# IGauge_V_2_0.net
KiCad netlist of a schematic drawn in EAGLE
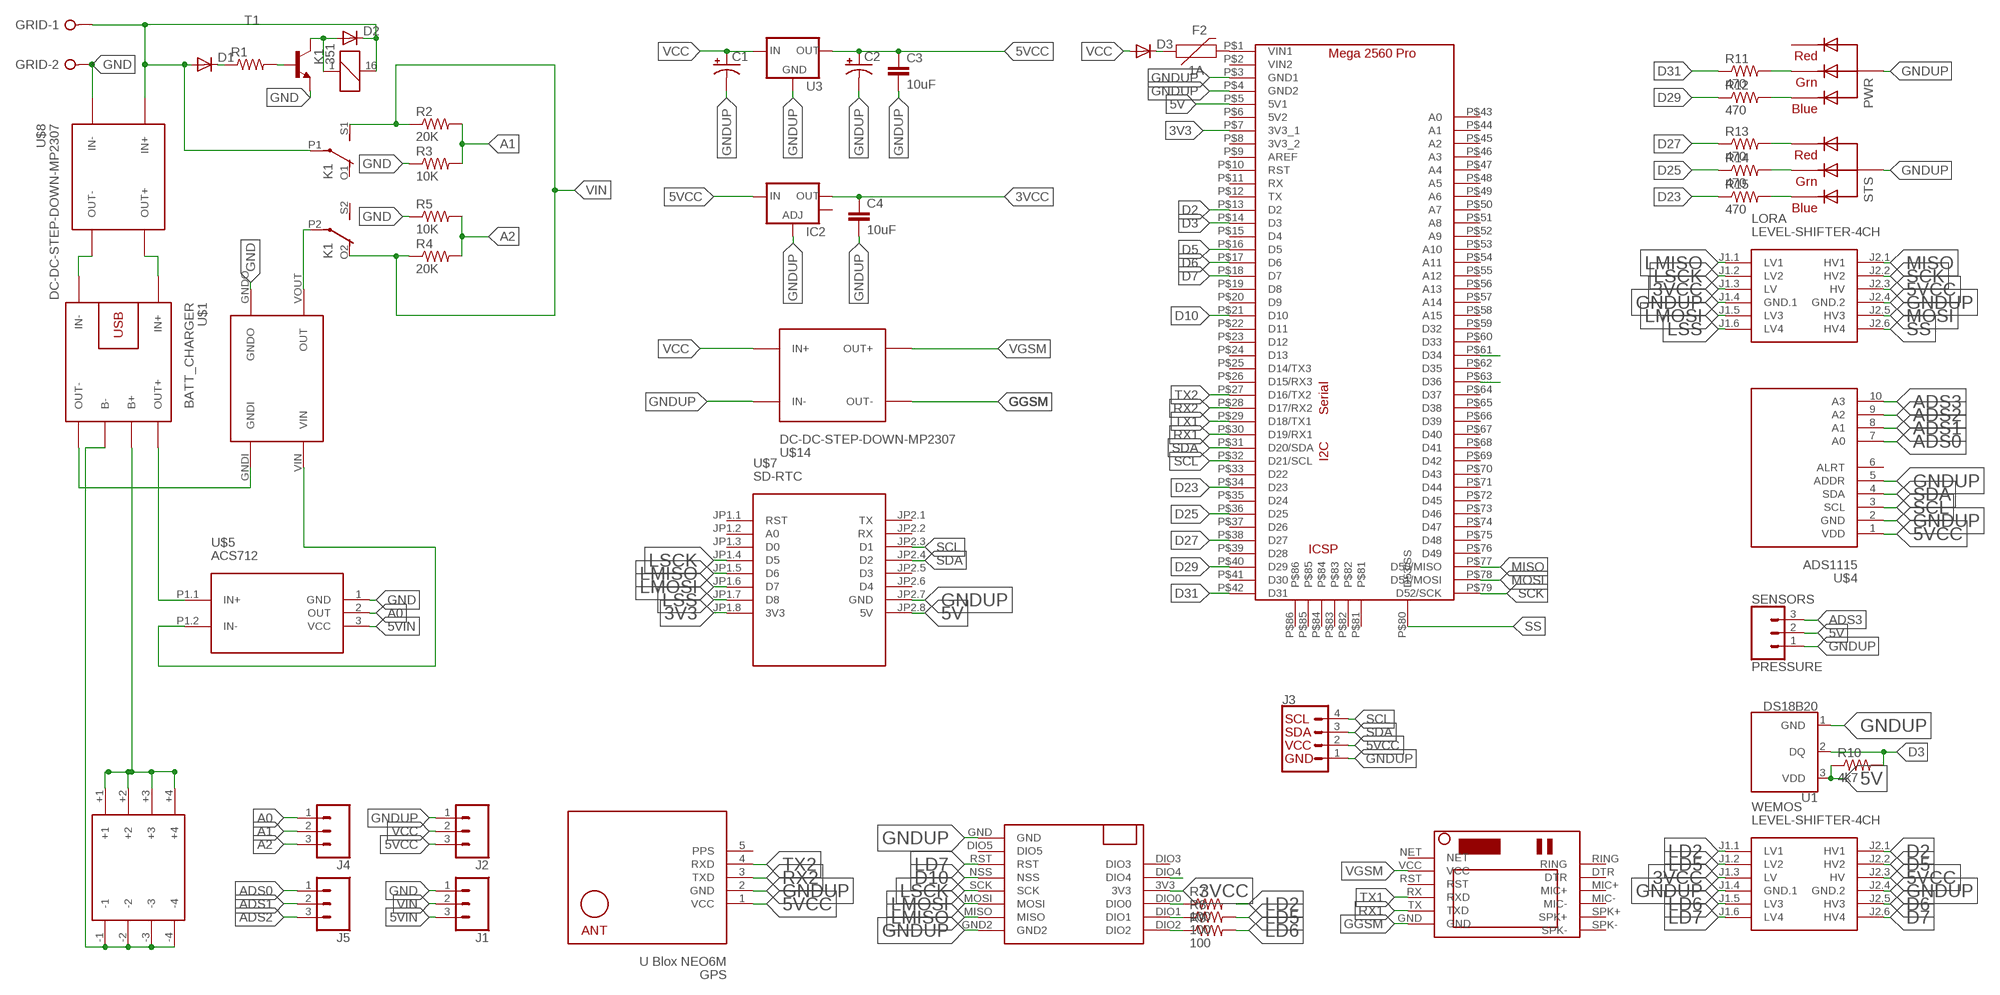
[diagram p0: schematic, sheet 1]

(export (version "E")
  (design (tool "Eeschema 10.0.6"))
  (components
    (comp (ref "C1")
      (value "CPOL-USD")
      (footprint "eagle-import:PANASONIC_D")
      (libsource (lib "eagle-import") (part "CPOL-USD"))
    )
    (comp (ref "C2")
      (value "CPOL-USD")
      (footprint "eagle-import:PANASONIC_D")
      (libsource (lib "eagle-import") (part "CPOL-USD"))
    )
    (comp (ref "C3")
      (value "10uF")
      (footprint "eagle-import:1206")
      (libsource (lib "eagle-import") (part "10UF-1206-6.3V-20%"))
    )
    (comp (ref "C4")
      (value "10uF")
      (footprint "eagle-import:1206")
      (libsource (lib "eagle-import") (part "10UF-1206-6.3V-20%"))
    )
    (comp (ref "D1")
      (value "DIODE-SOD106A-R")
      (footprint "eagle-import:SOD106A-R")
      (libsource (lib "eagle-import") (part "DIODE-SOD106A-R"))
    )
    (comp (ref "D2")
      (value "DIODE-SOD106A-R")
      (footprint "eagle-import:SOD106A-R")
      (libsource (lib "eagle-import") (part "DIODE-SOD106A-R"))
    )
    (comp (ref "D3")
      (value "DIODE-SOD106A-R")
      (footprint "eagle-import:SOD106A-R")
      (libsource (lib "eagle-import") (part "DIODE-SOD106A-R"))
    )
    (comp (ref "F2")
      (value "1A")
      (footprint "eagle-import:1206")
      (libsource (lib "eagle-import") (part "PPTC_HALF-AMP"))
    )
    (comp (ref "GPS")
      (value "U Blox NEO6M")
      (footprint "eagle-import:GPS-RECEIVER-NEO6M")
      (libsource (lib "eagle-import") (part "GPS-RECEIVER-NEO6M"))
    )
    (comp (ref "GRID")
      (value "W237-02P")
      (footprint "eagle-import:W237-132")
      (libsource (lib "eagle-import") (part "W237-02P"))
    )
    (comp (ref "IC2")
      (value "V_REG_LM1117SOT223")
      (footprint "eagle-import:SOT223")
      (libsource (lib "eagle-import") (part "V_REG_LM1117SOT223"))
    )
    (comp (ref "J1")
      (value "CONN_03")
      (footprint "eagle-import:1X03")
      (libsource (lib "eagle-import") (part "CONN_03"))
    )
    (comp (ref "J2")
      (value "CONN_03")
      (footprint "eagle-import:1X03")
      (libsource (lib "eagle-import") (part "CONN_03"))
    )
    (comp (ref "J3")
      (value "I2C_STANDARD")
      (footprint "eagle-import:1X04")
      (libsource (lib "eagle-import") (part "I2C_STANDARD"))
    )
    (comp (ref "J4")
      (value "CONN_03")
      (footprint "eagle-import:1X03")
      (libsource (lib "eagle-import") (part "CONN_03"))
    )
    (comp (ref "J5")
      (value "CONN_03")
      (footprint "eagle-import:1X03")
      (libsource (lib "eagle-import") (part "CONN_03"))
    )
    (comp (ref "K1")
      (value "351")
      (footprint "eagle-import:351")
      (libsource (lib "eagle-import") (part "351"))
    )
    (comp (ref "LORA")
      (value "LEVEL-SHIFTER-4CH")
      (footprint "eagle-import:LEVEL-SHIFTER-4CH")
      (libsource (lib "eagle-import") (part "LEVEL-SHIFTER-4CH"))
    )
    (comp (ref "PWR")
      (value "RGBLED_CA-5MM")
      (footprint "eagle-import:LED5MMRGB")
      (libsource (lib "eagle-import") (part "RGBLED_CA-5MM"))
    )
    (comp (ref "R1")
      (value "R-US_R1206")
      (footprint "eagle-import:R1206")
      (libsource (lib "eagle-import") (part "resistor_R-US_R1206"))
    )
    (comp (ref "R2")
      (value "20K")
      (footprint "eagle-import:R1206")
      (libsource (lib "eagle-import") (part "resistor_R-US_R1206"))
    )
    (comp (ref "R3")
      (value "10K")
      (footprint "eagle-import:R1206")
      (libsource (lib "eagle-import") (part "resistor_R-US_R1206"))
    )
    (comp (ref "R4")
      (value "20K")
      (footprint "eagle-import:R1206")
      (libsource (lib "eagle-import") (part "resistor_R-US_R1206"))
    )
    (comp (ref "R5")
      (value "10K")
      (footprint "eagle-import:R1206")
      (libsource (lib "eagle-import") (part "resistor_R-US_R1206"))
    )
    (comp (ref "R7")
      (value "100")
      (footprint "eagle-import:M1406")
      (libsource (lib "eagle-import") (part "R-US_M1406"))
    )
    (comp (ref "R8")
      (value "100")
      (footprint "eagle-import:M1406")
      (libsource (lib "eagle-import") (part "R-US_M1406"))
    )
    (comp (ref "R9")
      (value "100")
      (footprint "eagle-import:M1406")
      (libsource (lib "eagle-import") (part "R-US_M1406"))
    )
    (comp (ref "R10")
      (value "4k7")
      (footprint "eagle-import:M1406")
      (libsource (lib "eagle-import") (part "R-US_M1406"))
    )
    (comp (ref "R11")
      (value "470")
      (footprint "eagle-import:R1206")
      (libsource (lib "eagle-import") (part "resistor_R-US_R1206"))
    )
    (comp (ref "R12")
      (value "470")
      (footprint "eagle-import:R1206")
      (libsource (lib "eagle-import") (part "resistor_R-US_R1206"))
    )
    (comp (ref "R13")
      (value "470")
      (footprint "eagle-import:R1206")
      (libsource (lib "eagle-import") (part "resistor_R-US_R1206"))
    )
    (comp (ref "R14")
      (value "470")
      (footprint "eagle-import:R1206")
      (libsource (lib "eagle-import") (part "resistor_R-US_R1206"))
    )
    (comp (ref "R15")
      (value "470")
      (footprint "eagle-import:R1206")
      (libsource (lib "eagle-import") (part "resistor_R-US_R1206"))
    )
    (comp (ref "SENSORS")
      (value "PRESSURE")
      (footprint "eagle-import:MOLEX-1X3")
      (libsource (lib "eagle-import") (part "CONN_03POLAR"))
    )
    (comp (ref "STS")
      (value "RGBLED_CA-5MM")
      (footprint "eagle-import:LED5MMRGB")
      (libsource (lib "eagle-import") (part "RGBLED_CA-5MM"))
    )
    (comp (ref "T1")
      (value "-NPN-SOT23-EBC")
      (footprint "eagle-import:SOT23-EBC")
      (libsource (lib "eagle-import") (part "-NPN-SOT23-EBC"))
    )
    (comp (ref "U$1")
      (value "BATT_CHARGER")
      (footprint "eagle-import:BATTERY-CHARGER-LI-PROT")
      (libsource (lib "eagle-import") (part "BATTERY-CHARGER-LI-PROT"))
    )
    (comp (ref "U$2")
      (value "MT360_STEPUP")
      (footprint "eagle-import:MT360_STEPUP")
      (libsource (lib "eagle-import") (part "MT360_STEPUP"))
    )
    (comp (ref "U$3")
      (value "MEGAPROMINI")
      (footprint "eagle-import:MEGAPROMINI")
      (libsource (lib "eagle-import") (part "MEGAPROMINI"))
    )
    (comp (ref "U$4")
      (value "ADS1115")
      (footprint "eagle-import:ADC-4CH-ADS1115")
      (libsource (lib "eagle-import") (part "ADC-4CH-ADS1115"))
    )
    (comp (ref "U$5")
      (value "ACS712")
      (footprint "eagle-import:CURRENT-SENSOR-ACS712#IC")
      (libsource (lib "eagle-import") (part "CURRENT-SENSOR-ACS712#IC"))
    )
    (comp (ref "U$6")
      (value "LORA915MHZ")
      (footprint "eagle-import:LORA915MHZ")
      (libsource (lib "eagle-import") (part "LORA915MHZ"))
    )
    (comp (ref "U$7")
      (value "SD-RTC")
      (footprint "eagle-import:WEMOS-D1-MINI-SHIELD")
      (libsource (lib "eagle-import") (part "WEMOS-D1-MINI-SHIELD"))
    )
    (comp (ref "U$8")
      (value "DC-DC-STEP-DOWN-MP2307")
      (footprint "eagle-import:DC-DC-STEP-DOWN-MP2307")
      (libsource (lib "eagle-import") (part "DC-DC-STEP-DOWN-MP2307"))
    )
    (comp (ref "U$9")
      (value "18650_4PCS_BATTERY_HOLDER")
      (footprint "eagle-import:18650_4PCS_BATTERY_HOLDER")
      (libsource (lib "eagle-import") (part "18650_4PCS_BATTERY_HOLDER"))
    )
    (comp (ref "U$10")
      (value "SIM800LMODULE")
      (footprint "eagle-import:SIM800LMODULE")
      (libsource (lib "eagle-import") (part "SIM800LMODULE"))
    )
    (comp (ref "U$14")
      (value "DC-DC-STEP-DOWN-MP2307")
      (footprint "eagle-import:DC-DC-STEP-DOWN-MP2307")
      (libsource (lib "eagle-import") (part "DC-DC-STEP-DOWN-MP2307"))
    )
    (comp (ref "U1")
      (value "DS18B20")
      (footprint "eagle-import:TO-92-AMMO")
      (libsource (lib "eagle-import") (part "DS18B20"))
    )
    (comp (ref "U3")
      (value "V_REG_78XX-TO-220")
      (footprint "eagle-import:TO-220-ALT")
      (libsource (lib "eagle-import") (part "V_REG_78XX-TO-220"))
    )
    (comp (ref "WEMOS")
      (value "LEVEL-SHIFTER-4CH")
      (footprint "eagle-import:LEVEL-SHIFTER-4CH")
      (libsource (lib "eagle-import") (part "LEVEL-SHIFTER-4CH"))
    )
  )
  (nets
    (net (code "1") (name "/PPS") (class "Default")
      (node (ref "GPS") (pin "5") (pinfunction "PPS_5") (pintype "power_in"))
    )
    (net (code "2") (name "3V3") (class "Default")
      (node (ref "U$3") (pin "P$7") (pinfunction "3V3_1_P$7") (pintype "bidirectional"))
      (node (ref "U$7") (pin "JP1.8") (pinfunction "3V3_JP1.8") (pintype "power_in"))
    )
    (net (code "3") (name "3VCC") (class "Default")
      (node (ref "C4") (pin "1") (pinfunction "1_1") (pintype "passive"))
      (node (ref "IC2") (pin "2") (pinfunction "OUT_2") (pintype "output"))
      (node (ref "LORA") (pin "J1.3") (pinfunction "LV_J1.3") (pintype "power_in"))
      (node (ref "U$6") (pin "3V3") (pinfunction "3V3_3V3") (pintype "bidirectional"))
      (node (ref "WEMOS") (pin "J1.3") (pinfunction "LV_J1.3") (pintype "power_in"))
    )
    (net (code "4") (name "5V") (class "Default")
      (node (ref "R10") (pin "1") (pinfunction "1_1") (pintype "passive"))
      (node (ref "SENSORS") (pin "2") (pinfunction "2_2") (pintype "passive"))
      (node (ref "U$3") (pin "P$5") (pinfunction "5V1_P$5") (pintype "bidirectional"))
      (node (ref "U$7") (pin "JP2.8") (pinfunction "5V_JP2.8") (pintype "power_in"))
      (node (ref "U1") (pin "3") (pinfunction "VDD_3") (pintype "power_in"))
    )
    (net (code "5") (name "5VCC") (class "Default")
      (node (ref "C2") (pin "+") (pinfunction "+_+") (pintype "passive"))
      (node (ref "C3") (pin "1") (pinfunction "1_1") (pintype "passive"))
      (node (ref "GPS") (pin "1") (pinfunction "VCC_1") (pintype "bidirectional"))
      (node (ref "IC2") (pin "3") (pinfunction "IN_3") (pintype "input"))
      (node (ref "J2") (pin "3") (pinfunction "3_3") (pintype "passive"))
      (node (ref "J3") (pin "2") (pinfunction "2_2") (pintype "power_in"))
      (node (ref "LORA") (pin "J2.3") (pinfunction "HV_J2.3") (pintype "power_in"))
      (node (ref "U$4") (pin "1") (pinfunction "VDD_1") (pintype "power_in"))
      (node (ref "U3") (pin "OUT") (pinfunction "OUT_OUT") (pintype "passive"))
      (node (ref "WEMOS") (pin "J2.3") (pinfunction "HV_J2.3") (pintype "power_in"))
    )
    (net (code "6") (name "5VIN") (class "Default")
      (node (ref "J1") (pin "3") (pinfunction "3_3") (pintype "passive"))
      (node (ref "U$5") (pin "3") (pinfunction "VCC_3") (pintype "power_in"))
    )
    (net (code "7") (name "A0") (class "Default")
      (node (ref "J4") (pin "1") (pinfunction "1_1") (pintype "passive"))
      (node (ref "U$5") (pin "2") (pinfunction "OUT_2") (pintype "output"))
    )
    (net (code "8") (name "A1") (class "Default")
      (node (ref "J4") (pin "2") (pinfunction "2_2") (pintype "passive"))
      (node (ref "R2") (pin "2") (pinfunction "2_2") (pintype "passive"))
      (node (ref "R3") (pin "2") (pinfunction "2_2") (pintype "passive"))
    )
    (net (code "9") (name "A2") (class "Default")
      (node (ref "J4") (pin "3") (pinfunction "3_3") (pintype "passive"))
      (node (ref "R4") (pin "2") (pinfunction "2_2") (pintype "passive"))
      (node (ref "R5") (pin "2") (pinfunction "2_2") (pintype "passive"))
    )
    (net (code "10") (name "ADS0") (class "Default")
      (node (ref "J5") (pin "1") (pinfunction "1_1") (pintype "passive"))
      (node (ref "U$4") (pin "7") (pinfunction "A0_7") (pintype "input"))
    )
    (net (code "11") (name "ADS1") (class "Default")
      (node (ref "J5") (pin "2") (pinfunction "2_2") (pintype "passive"))
      (node (ref "U$4") (pin "8") (pinfunction "A1_8") (pintype "input"))
    )
    (net (code "12") (name "ADS2") (class "Default")
      (node (ref "J5") (pin "3") (pinfunction "3_3") (pintype "passive"))
      (node (ref "U$4") (pin "9") (pinfunction "A2_9") (pintype "input"))
    )
    (net (code "13") (name "ADS3") (class "Default")
      (node (ref "SENSORS") (pin "3") (pinfunction "3_3") (pintype "passive"))
      (node (ref "U$4") (pin "10") (pinfunction "A3_10") (pintype "input"))
    )
    (net (code "14") (name "D2") (class "Default")
      (node (ref "U$3") (pin "P$13") (pinfunction "D2_P$13") (pintype "bidirectional"))
      (node (ref "WEMOS") (pin "J2.1") (pinfunction "HV1_J2.1") (pintype "bidirectional"))
    )
    (net (code "15") (name "D3") (class "Default")
      (node (ref "R10") (pin "2") (pinfunction "2_2") (pintype "passive"))
      (node (ref "U$3") (pin "P$14") (pinfunction "D3_P$14") (pintype "bidirectional"))
      (node (ref "U1") (pin "2") (pinfunction "DQ_2") (pintype "bidirectional"))
    )
    (net (code "16") (name "D5") (class "Default")
      (node (ref "U$3") (pin "P$16") (pinfunction "D5_P$16") (pintype "bidirectional"))
      (node (ref "WEMOS") (pin "J2.2") (pinfunction "HV2_J2.2") (pintype "bidirectional"))
    )
    (net (code "17") (name "D6") (class "Default")
      (node (ref "U$3") (pin "P$17") (pinfunction "D6_P$17") (pintype "bidirectional"))
      (node (ref "WEMOS") (pin "J2.5") (pinfunction "HV3_J2.5") (pintype "bidirectional"))
    )
    (net (code "18") (name "D7") (class "Default")
      (node (ref "U$3") (pin "P$18") (pinfunction "D7_P$18") (pintype "bidirectional"))
      (node (ref "WEMOS") (pin "J2.6") (pinfunction "HV4_J2.6") (pintype "bidirectional"))
    )
    (net (code "19") (name "D10") (class "Default")
      (node (ref "U$3") (pin "P$21") (pinfunction "D10_P$21") (pintype "bidirectional"))
      (node (ref "U$6") (pin "NSS") (pinfunction "NSS_NSS") (pintype "bidirectional"))
    )
    (net (code "20") (name "D23") (class "Default")
      (node (ref "R15") (pin "1") (pinfunction "1_1") (pintype "passive"))
      (node (ref "U$3") (pin "P$34") (pinfunction "D23_P$34") (pintype "bidirectional"))
    )
    (net (code "21") (name "D25") (class "Default")
      (node (ref "R14") (pin "1") (pinfunction "1_1") (pintype "passive"))
      (node (ref "U$3") (pin "P$36") (pinfunction "D25_P$36") (pintype "bidirectional"))
    )
    (net (code "22") (name "D27") (class "Default")
      (node (ref "R13") (pin "1") (pinfunction "1_1") (pintype "passive"))
      (node (ref "U$3") (pin "P$38") (pinfunction "D27_P$38") (pintype "bidirectional"))
    )
    (net (code "23") (name "D29") (class "Default")
      (node (ref "R12") (pin "1") (pinfunction "1_1") (pintype "passive"))
      (node (ref "U$3") (pin "P$40") (pinfunction "D29_P$40") (pintype "bidirectional"))
    )
    (net (code "24") (name "D31") (class "Default")
      (node (ref "R11") (pin "1") (pinfunction "1_1") (pintype "passive"))
      (node (ref "U$3") (pin "P$42") (pinfunction "D31_P$42") (pintype "bidirectional"))
    )
    (net (code "25") (name "GGSM") (class "Default")
      (node (ref "U$10") (pin "GND") (pinfunction "GND_GND") (pintype "bidirectional"))
      (node (ref "U$14") (pin "OUT-") (pinfunction "OUT-_OUT-") (pintype "bidirectional"))
    )
    (net (code "26") (name "GND") (class "Default")
      (node (ref "D1") (pin "A") (pinfunction "A_A") (pintype "passive"))
      (node (ref "D2") (pin "C") (pinfunction "C_C") (pintype "passive"))
      (node (ref "GRID") (pin "1") (pinfunction "KL_1") (pintype "passive"))
      (node (ref "GRID") (pin "2") (pinfunction "KL_2") (pintype "passive"))
      (node (ref "J1") (pin "1") (pinfunction "1_1") (pintype "passive"))
      (node (ref "K1") (pin "16") (pinfunction "2_16") (pintype "passive"))
      (node (ref "K1") (pin "P1") (pinfunction "P_P1") (pintype "passive"))
      (node (ref "R3") (pin "1") (pinfunction "1_1") (pintype "passive"))
      (node (ref "R5") (pin "1") (pinfunction "1_1") (pintype "passive"))
      (node (ref "T1") (pin "E") (pinfunction "E_E") (pintype "passive"))
      (node (ref "U$2") (pin "GNDO") (pinfunction "GNDO_GNDO") (pintype "bidirectional"))
      (node (ref "U$5") (pin "1") (pinfunction "GND_1") (pintype "power_in"))
      (node (ref "U$8") (pin "IN+") (pinfunction "IN+_IN+") (pintype "bidirectional"))
      (node (ref "U$8") (pin "IN-") (pinfunction "IN-_IN-") (pintype "bidirectional"))
    )
    (net (code "27") (name "GNDUP") (class "Default")
      (node (ref "C1") (pin "-") (pinfunction "-_-") (pintype "passive"))
      (node (ref "C2") (pin "-") (pinfunction "-_-") (pintype "passive"))
      (node (ref "C3") (pin "2") (pinfunction "2_2") (pintype "passive"))
      (node (ref "C4") (pin "2") (pinfunction "2_2") (pintype "passive"))
      (node (ref "GPS") (pin "2") (pinfunction "GND_2") (pintype "bidirectional"))
      (node (ref "IC2") (pin "1") (pinfunction "ADJ_1") (pintype "input"))
      (node (ref "J2") (pin "1") (pinfunction "1_1") (pintype "passive"))
      (node (ref "J3") (pin "1") (pinfunction "1_1") (pintype "power_in"))
      (node (ref "LORA") (pin "J1.4") (pinfunction "GND.1_J1.4") (pintype "power_in"))
      (node (ref "LORA") (pin "J2.4") (pinfunction "GND.2_J2.4") (pintype "power_in"))
      (node (ref "PWR") (pin "2") (pinfunction "VCC_2") (pintype "bidirectional"))
      (node (ref "SENSORS") (pin "1") (pinfunction "1_1") (pintype "passive"))
      (node (ref "STS") (pin "2") (pinfunction "VCC_2") (pintype "bidirectional"))
      (node (ref "U$1") (pin "IN-") (pinfunction "IN-_IN-") (pintype "bidirectional"))
      (node (ref "U$14") (pin "IN-") (pinfunction "IN-_IN-") (pintype "bidirectional"))
      (node (ref "U$3") (pin "P$3") (pinfunction "GND1_P$3") (pintype "bidirectional"))
      (node (ref "U$3") (pin "P$4") (pinfunction "GND2_P$4") (pintype "bidirectional"))
      (node (ref "U$4") (pin "2") (pinfunction "GND_2") (pintype "power_in"))
      (node (ref "U$4") (pin "5") (pinfunction "ADDR_5") (pintype "bidirectional"))
      (node (ref "U$6") (pin "GND") (pinfunction "GND_GND") (pintype "bidirectional"))
      (node (ref "U$6") (pin "GND2") (pinfunction "GND2_GND2") (pintype "bidirectional"))
      (node (ref "U$7") (pin "JP2.7") (pinfunction "GND_JP2.7") (pintype "power_in"))
      (node (ref "U$8") (pin "OUT-") (pinfunction "OUT-_OUT-") (pintype "bidirectional"))
      (node (ref "U1") (pin "1") (pinfunction "GND_1") (pintype "power_in"))
      (node (ref "U3") (pin "GND") (pinfunction "GND_GND") (pintype "input"))
      (node (ref "WEMOS") (pin "J1.4") (pinfunction "GND.1_J1.4") (pintype "power_in"))
      (node (ref "WEMOS") (pin "J2.4") (pinfunction "GND.2_J2.4") (pintype "power_in"))
    )
    (net (code "28") (name "LD2") (class "Default")
      (node (ref "R7") (pin "2") (pinfunction "2_2") (pintype "passive"))
      (node (ref "WEMOS") (pin "J1.1") (pinfunction "LV1_J1.1") (pintype "bidirectional"))
    )
    (net (code "29") (name "LD5") (class "Default")
      (node (ref "R8") (pin "2") (pinfunction "2_2") (pintype "passive"))
      (node (ref "WEMOS") (pin "J1.2") (pinfunction "LV2_J1.2") (pintype "bidirectional"))
    )
    (net (code "30") (name "LD6") (class "Default")
      (node (ref "R9") (pin "2") (pinfunction "2_2") (pintype "passive"))
      (node (ref "WEMOS") (pin "J1.5") (pinfunction "LV3_J1.5") (pintype "bidirectional"))
    )
    (net (code "31") (name "LD7") (class "Default")
      (node (ref "U$6") (pin "RST") (pinfunction "RST_RST") (pintype "bidirectional"))
      (node (ref "WEMOS") (pin "J1.6") (pinfunction "LV4_J1.6") (pintype "bidirectional"))
    )
    (net (code "32") (name "LMISO") (class "Default")
      (node (ref "LORA") (pin "J1.1") (pinfunction "LV1_J1.1") (pintype "bidirectional"))
      (node (ref "U$6") (pin "MISO") (pinfunction "MISO_MISO") (pintype "bidirectional"))
      (node (ref "U$7") (pin "JP1.5") (pinfunction "D6_JP1.5") (pintype "bidirectional"))
    )
    (net (code "33") (name "LMOSI") (class "Default")
      (node (ref "LORA") (pin "J1.5") (pinfunction "LV3_J1.5") (pintype "bidirectional"))
      (node (ref "U$6") (pin "MOSI") (pinfunction "MOSI_MOSI") (pintype "bidirectional"))
      (node (ref "U$7") (pin "JP1.6") (pinfunction "D7_JP1.6") (pintype "bidirectional"))
    )
    (net (code "34") (name "LSCK") (class "Default")
      (node (ref "LORA") (pin "J1.2") (pinfunction "LV2_J1.2") (pintype "bidirectional"))
      (node (ref "U$6") (pin "SCK") (pinfunction "SCK_SCK") (pintype "bidirectional"))
      (node (ref "U$7") (pin "JP1.4") (pinfunction "D5_JP1.4") (pintype "bidirectional"))
    )
    (net (code "35") (name "LSS") (class "Default")
      (node (ref "LORA") (pin "J1.6") (pinfunction "LV4_J1.6") (pintype "bidirectional"))
      (node (ref "U$7") (pin "JP1.7") (pinfunction "D8_JP1.7") (pintype "bidirectional"))
    )
    (net (code "36") (name "MISO") (class "Default")
      (node (ref "LORA") (pin "J2.1") (pinfunction "HV1_J2.1") (pintype "bidirectional"))
      (node (ref "U$3") (pin "P$77") (pinfunction "D50/MISO_P$77") (pintype "bidirectional"))
    )
    (net (code "37") (name "MOSI") (class "Default")
      (node (ref "LORA") (pin "J2.5") (pinfunction "HV3_J2.5") (pintype "bidirectional"))
      (node (ref "U$3") (pin "P$78") (pinfunction "D51/MOSI_P$78") (pintype "bidirectional"))
    )
    (net (code "38") (name "Net-(D1-PadC)") (class "Default")
      (node (ref "D1") (pin "C") (pinfunction "C_C") (pintype "passive"))
      (node (ref "R1") (pin "1") (pinfunction "1_1") (pintype "passive"))
    )
    (net (code "39") (name "Net-(D2-PadA)") (class "Default")
      (node (ref "D2") (pin "A") (pinfunction "A_A") (pintype "passive"))
      (node (ref "K1") (pin "1") (pinfunction "1_1") (pintype "passive"))
      (node (ref "T1") (pin "C") (pinfunction "C_C") (pintype "passive"))
    )
    (net (code "40") (name "Net-(D3-PadC)") (class "Default")
      (node (ref "D3") (pin "C") (pinfunction "C_C") (pintype "passive"))
      (node (ref "F2") (pin "1") (pinfunction "1_1") (pintype "bidirectional"))
    )
    (net (code "41") (name "Net-(K1C-P)") (class "Default")
      (node (ref "K1") (pin "P2") (pinfunction "P_P2") (pintype "passive"))
      (node (ref "U$2") (pin "VOUT") (pinfunction "OUT_VOUT") (pintype "bidirectional"))
    )
    (net (code "42") (name "Net-(PWR-BLUE)") (class "Default")
      (node (ref "PWR") (pin "4") (pinfunction "BLUE_4") (pintype "bidirectional"))
      (node (ref "R12") (pin "2") (pinfunction "2_2") (pintype "passive"))
    )
    (net (code "43") (name "Net-(PWR-GREEN)") (class "Default")
      (node (ref "PWR") (pin "3") (pinfunction "GREEN_3") (pintype "bidirectional"))
      (node (ref "R11") (pin "2") (pinfunction "2_2") (pintype "passive"))
    )
    (net (code "44") (name "Net-(R1-Pad2)") (class "Default")
      (node (ref "R1") (pin "2") (pinfunction "2_2") (pintype "passive"))
      (node (ref "T1") (pin "B") (pinfunction "B_B") (pintype "passive"))
    )
    (net (code "45") (name "Net-(R7-Pad1)") (class "Default")
      (node (ref "R7") (pin "1") (pinfunction "1_1") (pintype "passive"))
      (node (ref "U$6") (pin "DIO0") (pinfunction "DIO0_DIO0") (pintype "bidirectional"))
    )
    (net (code "46") (name "Net-(R8-Pad1)") (class "Default")
      (node (ref "R8") (pin "1") (pinfunction "1_1") (pintype "passive"))
      (node (ref "U$6") (pin "DIO1") (pinfunction "DIO1_DIO1") (pintype "bidirectional"))
    )
    (net (code "47") (name "Net-(R9-Pad1)") (class "Default")
      (node (ref "R9") (pin "1") (pinfunction "1_1") (pintype "passive"))
      (node (ref "U$6") (pin "DIO2") (pinfunction "DIO2_DIO2") (pintype "bidirectional"))
    )
    (net (code "48") (name "Net-(STS-BLUE)") (class "Default")
      (node (ref "R15") (pin "2") (pinfunction "2_2") (pintype "passive"))
      (node (ref "STS") (pin "4") (pinfunction "BLUE_4") (pintype "bidirectional"))
    )
    (net (code "49") (name "Net-(STS-GREEN)") (class "Default")
      (node (ref "R14") (pin "2") (pinfunction "2_2") (pintype "passive"))
      (node (ref "STS") (pin "3") (pinfunction "GREEN_3") (pintype "bidirectional"))
    )
    (net (code "50") (name "Net-(STS-RED)") (class "Default")
      (node (ref "R13") (pin "2") (pinfunction "2_2") (pintype "passive"))
      (node (ref "STS") (pin "1") (pinfunction "RED_1") (pintype "bidirectional"))
    )
    (net (code "51") (name "Net-(U$1-PadB+)") (class "Default")
      (node (ref "U$1") (pin "B+") (pinfunction "B+_B+") (pintype "bidirectional"))
      (node (ref "U$9") (pin "+1") (pinfunction "+1_+1") (pintype "bidirectional"))
      (node (ref "U$9") (pin "+2") (pinfunction "+2_+2") (pintype "bidirectional"))
      (node (ref "U$9") (pin "+3") (pinfunction "+3_+3") (pintype "bidirectional"))
      (node (ref "U$9") (pin "+4") (pinfunction "+4_+4") (pintype "bidirectional"))
    )
    (net (code "52") (name "Net-(U$1-PadB-)") (class "Default")
      (node (ref "U$1") (pin "B-") (pinfunction "B-_B-") (pintype "bidirectional"))
      (node (ref "U$9") (pin "-1") (pinfunction "-1_-1") (pintype "bidirectional"))
      (node (ref "U$9") (pin "-2") (pinfunction "-2_-2") (pintype "bidirectional"))
      (node (ref "U$9") (pin "-3") (pinfunction "-3_-3") (pintype "bidirectional"))
      (node (ref "U$9") (pin "-4") (pinfunction "-4_-4") (pintype "bidirectional"))
    )
    (net (code "53") (name "Net-(U$1-PadIN+)") (class "Default")
      (node (ref "U$1") (pin "IN+") (pinfunction "IN+_IN+") (pintype "bidirectional"))
      (node (ref "U$8") (pin "OUT+") (pinfunction "OUT+_OUT+") (pintype "bidirectional"))
    )
    (net (code "54") (name "Net-(U$1-PadOUT-)") (class "Default")
      (node (ref "U$1") (pin "OUT-") (pinfunction "OUT-_OUT-") (pintype "bidirectional"))
      (node (ref "U$2") (pin "GNDI") (pinfunction "GNDI_GNDI") (pintype "bidirectional"))
    )
    (net (code "55") (name "Net-(U$3-VIN1)") (class "Default")
      (node (ref "F2") (pin "2") (pinfunction "2_2") (pintype "bidirectional"))
      (node (ref "U$3") (pin "P$1") (pinfunction "VIN1_P$1") (pintype "bidirectional"))
    )
    (net (code "56") (name "Net-(U$5-IN+)") (class "Default")
      (node (ref "U$1") (pin "OUT+") (pinfunction "OUT+_OUT+") (pintype "bidirectional"))
      (node (ref "U$5") (pin "P1.1") (pinfunction "IN+_P1.1") (pintype "bidirectional"))
    )
    (net (code "57") (name "Net-(U$5-IN-)") (class "Default")
      (node (ref "U$2") (pin "VIN") (pinfunction "VIN_VIN") (pintype "bidirectional"))
      (node (ref "U$5") (pin "P1.2") (pinfunction "IN-_P1.2") (pintype "bidirectional"))
    )
    (net (code "58") (name "RX1") (class "Default")
      (node (ref "U$10") (pin "TX") (pinfunction "TXD_TX") (pintype "bidirectional"))
      (node (ref "U$3") (pin "P$30") (pinfunction "D19/RX1_P$30") (pintype "bidirectional"))
    )
    (net (code "59") (name "RX2") (class "Default")
      (node (ref "GPS") (pin "3") (pinfunction "TXD_3") (pintype "bidirectional"))
      (node (ref "U$3") (pin "P$28") (pinfunction "D17/RX2_P$28") (pintype "bidirectional"))
    )
    (net (code "60") (name "SCK") (class "Default")
      (node (ref "LORA") (pin "J2.2") (pinfunction "HV2_J2.2") (pintype "bidirectional"))
      (node (ref "U$3") (pin "P$79") (pinfunction "D52/SCK_P$79") (pintype "bidirectional"))
    )
    (net (code "61") (name "SCL") (class "Default")
      (node (ref "J3") (pin "4") (pinfunction "4_4") (pintype "passive"))
      (node (ref "U$3") (pin "P$32") (pinfunction "D21/SCL_P$32") (pintype "bidirectional"))
      (node (ref "U$4") (pin "3") (pinfunction "SCL_3") (pintype "bidirectional"))
      (node (ref "U$7") (pin "JP2.3") (pinfunction "D1_JP2.3") (pintype "bidirectional"))
    )
    (net (code "62") (name "SDA") (class "Default")
      (node (ref "J3") (pin "3") (pinfunction "3_3") (pintype "passive"))
      (node (ref "U$3") (pin "P$31") (pinfunction "D20/SDA_P$31") (pintype "bidirectional"))
      (node (ref "U$4") (pin "4") (pinfunction "SDA_4") (pintype "bidirectional"))
      (node (ref "U$7") (pin "JP2.4") (pinfunction "D2_JP2.4") (pintype "bidirectional"))
    )
    (net (code "63") (name "SS") (class "Default")
      (node (ref "LORA") (pin "J2.6") (pinfunction "HV4_J2.6") (pintype "bidirectional"))
      (node (ref "U$3") (pin "P$80") (pinfunction "D53/SS_P$80") (pintype "bidirectional"))
    )
    (net (code "64") (name "TX1") (class "Default")
      (node (ref "U$10") (pin "RX") (pinfunction "RXD_RX") (pintype "bidirectional"))
      (node (ref "U$3") (pin "P$29") (pinfunction "D18/TX1_P$29") (pintype "bidirectional"))
    )
    (net (code "65") (name "TX2") (class "Default")
      (node (ref "GPS") (pin "4") (pinfunction "RXD_4") (pintype "power_in"))
      (node (ref "U$3") (pin "P$27") (pinfunction "D16/TX2_P$27") (pintype "bidirectional"))
    )
    (net (code "66") (name "VCC") (class "Default")
      (node (ref "C1") (pin "+") (pinfunction "+_+") (pintype "passive"))
      (node (ref "D3") (pin "A") (pinfunction "A_A") (pintype "passive"))
      (node (ref "J2") (pin "2") (pinfunction "2_2") (pintype "passive"))
      (node (ref "U$14") (pin "IN+") (pinfunction "IN+_IN+") (pintype "bidirectional"))
      (node (ref "U3") (pin "IN") (pinfunction "IN_IN") (pintype "input"))
    )
    (net (code "67") (name "VGSM") (class "Default")
      (node (ref "U$10") (pin "VCC") (pinfunction "VCC_VCC") (pintype "bidirectional"))
      (node (ref "U$14") (pin "OUT+") (pinfunction "OUT+_OUT+") (pintype "bidirectional"))
    )
    (net (code "68") (name "VIN") (class "Default")
      (node (ref "J1") (pin "2") (pinfunction "2_2") (pintype "passive"))
      (node (ref "K1") (pin "O2") (pinfunction "O_O2") (pintype "passive"))
      (node (ref "K1") (pin "S1") (pinfunction "S_S1") (pintype "passive"))
      (node (ref "R2") (pin "1") (pinfunction "1_1") (pintype "passive"))
      (node (ref "R4") (pin "1") (pinfunction "1_1") (pintype "passive"))
    )
    (net (code "69") (name "unconnected-(IC2-OUT-Pad4)") (class "Default")
      (node (ref "IC2") (pin "4") (pinfunction "OUT_4") (pintype "output"))
    )
    (net (code "70") (name "unconnected-(K1B-O-PadO1)") (class "Default")
      (node (ref "K1") (pin "O1") (pinfunction "O_O1") (pintype "passive"))
    )
    (net (code "71") (name "unconnected-(K1C-S-PadS2)") (class "Default")
      (node (ref "K1") (pin "S2") (pinfunction "S_S2") (pintype "passive"))
    )
    (net (code "72") (name "unconnected-(PWR-RED-Pad1)") (class "Default")
      (node (ref "PWR") (pin "1") (pinfunction "RED_1") (pintype "bidirectional"))
    )
    (net (code "73") (name "unconnected-(U$3-3V3_2-PadP$8)") (class "Default")
      (node (ref "U$3") (pin "P$8") (pinfunction "3V3_2_P$8") (pintype "bidirectional"))
    )
    (net (code "74") (name "unconnected-(U$3-5V2-PadP$6)") (class "Default")
      (node (ref "U$3") (pin "P$6") (pinfunction "5V2_P$6") (pintype "bidirectional"))
    )
    (net (code "75") (name "unconnected-(U$3-A0-PadP$43)") (class "Default")
      (node (ref "U$3") (pin "P$43") (pinfunction "A0_P$43") (pintype "bidirectional"))
    )
    (net (code "76") (name "unconnected-(U$3-A1-PadP$44)") (class "Default")
      (node (ref "U$3") (pin "P$44") (pinfunction "A1_P$44") (pintype "bidirectional"))
    )
    (net (code "77") (name "unconnected-(U$3-A2-PadP$45)") (class "Default")
      (node (ref "U$3") (pin "P$45") (pinfunction "A2_P$45") (pintype "bidirectional"))
    )
    (net (code "78") (name "unconnected-(U$3-A3-PadP$46)") (class "Default")
      (node (ref "U$3") (pin "P$46") (pinfunction "A3_P$46") (pintype "bidirectional"))
    )
    (net (code "79") (name "unconnected-(U$3-A4-PadP$47)") (class "Default")
      (node (ref "U$3") (pin "P$47") (pinfunction "A4_P$47") (pintype "bidirectional"))
    )
    (net (code "80") (name "unconnected-(U$3-A5-PadP$48)") (class "Default")
      (node (ref "U$3") (pin "P$48") (pinfunction "A5_P$48") (pintype "bidirectional"))
    )
    (net (code "81") (name "unconnected-(U$3-A6-PadP$49)") (class "Default")
      (node (ref "U$3") (pin "P$49") (pinfunction "A6_P$49") (pintype "bidirectional"))
    )
    (net (code "82") (name "unconnected-(U$3-A7-PadP$50)") (class "Default")
      (node (ref "U$3") (pin "P$50") (pinfunction "A7_P$50") (pintype "bidirectional"))
    )
    (net (code "83") (name "unconnected-(U$3-A8-PadP$51)") (class "Default")
      (node (ref "U$3") (pin "P$51") (pinfunction "A8_P$51") (pintype "bidirectional"))
    )
    (net (code "84") (name "unconnected-(U$3-A9-PadP$52)") (class "Default")
      (node (ref "U$3") (pin "P$52") (pinfunction "A9_P$52") (pintype "bidirectional"))
    )
    (net (code "85") (name "unconnected-(U$3-A10-PadP$53)") (class "Default")
      (node (ref "U$3") (pin "P$53") (pinfunction "A10_P$53") (pintype "bidirectional"))
    )
    (net (code "86") (name "unconnected-(U$3-A11-PadP$54)") (class "Default")
      (node (ref "U$3") (pin "P$54") (pinfunction "A11_P$54") (pintype "bidirectional"))
    )
    (net (code "87") (name "unconnected-(U$3-A12-PadP$55)") (class "Default")
      (node (ref "U$3") (pin "P$55") (pinfunction "A12_P$55") (pintype "bidirectional"))
    )
    (net (code "88") (name "unconnected-(U$3-A13-PadP$56)") (class "Default")
      (node (ref "U$3") (pin "P$56") (pinfunction "A13_P$56") (pintype "bidirectional"))
    )
    (net (code "89") (name "unconnected-(U$3-A14-PadP$57)") (class "Default")
      (node (ref "U$3") (pin "P$57") (pinfunction "A14_P$57") (pintype "bidirectional"))
    )
    (net (code "90") (name "unconnected-(U$3-A15-PadP$58)") (class "Default")
      (node (ref "U$3") (pin "P$58") (pinfunction "A15_P$58") (pintype "bidirectional"))
    )
    (net (code "91") (name "unconnected-(U$3-AREF-PadP$9)") (class "Default")
      (node (ref "U$3") (pin "P$9") (pinfunction "AREF_P$9") (pintype "bidirectional"))
    )
    (net (code "92") (name "unconnected-(U$3-D4-PadP$15)") (class "Default")
      (node (ref "U$3") (pin "P$15") (pinfunction "D4_P$15") (pintype "bidirectional"))
    )
    (net (code "93") (name "unconnected-(U$3-D8-PadP$19)") (class "Default")
      (node (ref "U$3") (pin "P$19") (pinfunction "D8_P$19") (pintype "bidirectional"))
    )
    (net (code "94") (name "unconnected-(U$3-D9-PadP$20)") (class "Default")
      (node (ref "U$3") (pin "P$20") (pinfunction "D9_P$20") (pintype "bidirectional"))
    )
    (net (code "95") (name "unconnected-(U$3-D11-PadP$22)") (class "Default")
      (node (ref "U$3") (pin "P$22") (pinfunction "D11_P$22") (pintype "bidirectional"))
    )
    (net (code "96") (name "unconnected-(U$3-D12-PadP$23)") (class "Default")
      (node (ref "U$3") (pin "P$23") (pinfunction "D12_P$23") (pintype "bidirectional"))
    )
    (net (code "97") (name "unconnected-(U$3-D13-PadP$24)") (class "Default")
      (node (ref "U$3") (pin "P$24") (pinfunction "D13_P$24") (pintype "bidirectional"))
    )
    (net (code "98") (name "unconnected-(U$3-D14{slash}TX3-PadP$25)") (class "Default")
      (node (ref "U$3") (pin "P$25") (pinfunction "D14/TX3_P$25") (pintype "bidirectional"))
    )
    (net (code "99") (name "unconnected-(U$3-D15{slash}RX3-PadP$26)") (class "Default")
      (node (ref "U$3") (pin "P$26") (pinfunction "D15/RX3_P$26") (pintype "bidirectional"))
    )
    (net (code "100") (name "unconnected-(U$3-D22-PadP$33)") (class "Default")
      (node (ref "U$3") (pin "P$33") (pinfunction "D22_P$33") (pintype "bidirectional"))
    )
    (net (code "101") (name "unconnected-(U$3-D24-PadP$35)") (class "Default")
      (node (ref "U$3") (pin "P$35") (pinfunction "D24_P$35") (pintype "bidirectional"))
    )
    (net (code "102") (name "unconnected-(U$3-D26-PadP$37)") (class "Default")
      (node (ref "U$3") (pin "P$37") (pinfunction "D26_P$37") (pintype "bidirectional"))
    )
    (net (code "103") (name "unconnected-(U$3-D28-PadP$39)") (class "Default")
      (node (ref "U$3") (pin "P$39") (pinfunction "D28_P$39") (pintype "bidirectional"))
    )
    (net (code "104") (name "unconnected-(U$3-D30-PadP$41)") (class "Default")
      (node (ref "U$3") (pin "P$41") (pinfunction "D30_P$41") (pintype "bidirectional"))
    )
    (net (code "105") (name "unconnected-(U$3-D32-PadP$59)") (class "Default")
      (node (ref "U$3") (pin "P$59") (pinfunction "D32_P$59") (pintype "bidirectional"))
    )
    (net (code "106") (name "unconnected-(U$3-D33-PadP$60)") (class "Default")
      (node (ref "U$3") (pin "P$60") (pinfunction "D33_P$60") (pintype "bidirectional"))
    )
    (net (code "107") (name "unconnected-(U$3-D34-PadP$61)") (class "Default")
      (node (ref "U$3") (pin "P$61") (pinfunction "D34_P$61") (pintype "bidirectional"))
    )
    (net (code "108") (name "unconnected-(U$3-D35-PadP$62)") (class "Default")
      (node (ref "U$3") (pin "P$62") (pinfunction "D35_P$62") (pintype "bidirectional"))
    )
    (net (code "109") (name "unconnected-(U$3-D36-PadP$63)") (class "Default")
      (node (ref "U$3") (pin "P$63") (pinfunction "D36_P$63") (pintype "bidirectional"))
    )
    (net (code "110") (name "unconnected-(U$3-D37-PadP$64)") (class "Default")
      (node (ref "U$3") (pin "P$64") (pinfunction "D37_P$64") (pintype "bidirectional"))
    )
    (net (code "111") (name "unconnected-(U$3-D38-PadP$65)") (class "Default")
      (node (ref "U$3") (pin "P$65") (pinfunction "D38_P$65") (pintype "bidirectional"))
    )
    (net (code "112") (name "unconnected-(U$3-D39-PadP$66)") (class "Default")
      (node (ref "U$3") (pin "P$66") (pinfunction "D39_P$66") (pintype "bidirectional"))
    )
    (net (code "113") (name "unconnected-(U$3-D40-PadP$67)") (class "Default")
      (node (ref "U$3") (pin "P$67") (pinfunction "D40_P$67") (pintype "bidirectional"))
    )
    (net (code "114") (name "unconnected-(U$3-D41-PadP$68)") (class "Default")
      (node (ref "U$3") (pin "P$68") (pinfunction "D41_P$68") (pintype "bidirectional"))
    )
    (net (code "115") (name "unconnected-(U$3-D42-PadP$69)") (class "Default")
      (node (ref "U$3") (pin "P$69") (pinfunction "D42_P$69") (pintype "bidirectional"))
    )
    (net (code "116") (name "unconnected-(U$3-D43-PadP$70)") (class "Default")
      (node (ref "U$3") (pin "P$70") (pinfunction "D43_P$70") (pintype "bidirectional"))
    )
    (net (code "117") (name "unconnected-(U$3-D44-PadP$71)") (class "Default")
      (node (ref "U$3") (pin "P$71") (pinfunction "D44_P$71") (pintype "bidirectional"))
    )
    (net (code "118") (name "unconnected-(U$3-D45-PadP$72)") (class "Default")
      (node (ref "U$3") (pin "P$72") (pinfunction "D45_P$72") (pintype "bidirectional"))
    )
    (net (code "119") (name "unconnected-(U$3-D46-PadP$73)") (class "Default")
      (node (ref "U$3") (pin "P$73") (pinfunction "D46_P$73") (pintype "bidirectional"))
    )
    (net (code "120") (name "unconnected-(U$3-D47-PadP$74)") (class "Default")
      (node (ref "U$3") (pin "P$74") (pinfunction "D47_P$74") (pintype "bidirectional"))
    )
    (net (code "121") (name "unconnected-(U$3-D48-PadP$75)") (class "Default")
      (node (ref "U$3") (pin "P$75") (pinfunction "D48_P$75") (pintype "bidirectional"))
    )
    (net (code "122") (name "unconnected-(U$3-D49-PadP$76)") (class "Default")
      (node (ref "U$3") (pin "P$76") (pinfunction "D49_P$76") (pintype "bidirectional"))
    )
    (net (code "123") (name "unconnected-(U$3-PadP$81)") (class "Default")
      (node (ref "U$3") (pin "P$81") (pinfunction "P$81_P$81") (pintype "bidirectional"))
    )
    (net (code "124") (name "unconnected-(U$3-PadP$82)") (class "Default")
      (node (ref "U$3") (pin "P$82") (pinfunction "P$82_P$82") (pintype "bidirectional"))
    )
    (net (code "125") (name "unconnected-(U$3-PadP$83)") (class "Default")
      (node (ref "U$3") (pin "P$83") (pinfunction "P$83_P$83") (pintype "bidirectional"))
    )
    (net (code "126") (name "unconnected-(U$3-PadP$84)") (class "Default")
      (node (ref "U$3") (pin "P$84") (pinfunction "P$84_P$84") (pintype "bidirectional"))
    )
    (net (code "127") (name "unconnected-(U$3-PadP$85)") (class "Default")
      (node (ref "U$3") (pin "P$85") (pinfunction "P$85_P$85") (pintype "bidirectional"))
    )
    (net (code "128") (name "unconnected-(U$3-PadP$86)") (class "Default")
      (node (ref "U$3") (pin "P$86") (pinfunction "P$86_P$86") (pintype "bidirectional"))
    )
    (net (code "129") (name "unconnected-(U$3-RST-PadP$10)") (class "Default")
      (node (ref "U$3") (pin "P$10") (pinfunction "RST_P$10") (pintype "bidirectional"))
    )
    (net (code "130") (name "unconnected-(U$3-RX-PadP$11)") (class "Default")
      (node (ref "U$3") (pin "P$11") (pinfunction "RX_P$11") (pintype "bidirectional"))
    )
    (net (code "131") (name "unconnected-(U$3-TX-PadP$12)") (class "Default")
      (node (ref "U$3") (pin "P$12") (pinfunction "TX_P$12") (pintype "bidirectional"))
    )
    (net (code "132") (name "unconnected-(U$3-VIN2-PadP$2)") (class "Default")
      (node (ref "U$3") (pin "P$2") (pinfunction "VIN2_P$2") (pintype "bidirectional"))
    )
    (net (code "133") (name "unconnected-(U$4-ALRT-Pad6)") (class "Default")
      (node (ref "U$4") (pin "6") (pinfunction "ALRT_6") (pintype "bidirectional"))
    )
    (net (code "134") (name "unconnected-(U$6-PadDIO3)") (class "Default")
      (node (ref "U$6") (pin "DIO3") (pinfunction "DIO3_DIO3") (pintype "bidirectional"))
    )
    (net (code "135") (name "unconnected-(U$6-PadDIO4)") (class "Default")
      (node (ref "U$6") (pin "DIO4") (pinfunction "DIO4_DIO4") (pintype "bidirectional"))
    )
    (net (code "136") (name "unconnected-(U$6-PadDIO5)") (class "Default")
      (node (ref "U$6") (pin "DIO5") (pinfunction "DIO5_DIO5") (pintype "bidirectional"))
    )
    (net (code "137") (name "unconnected-(U$7-A0-PadJP1.2)") (class "Default")
      (node (ref "U$7") (pin "JP1.2") (pinfunction "A0_JP1.2") (pintype "bidirectional"))
    )
    (net (code "138") (name "unconnected-(U$7-D0-PadJP1.3)") (class "Default")
      (node (ref "U$7") (pin "JP1.3") (pinfunction "D0_JP1.3") (pintype "bidirectional"))
    )
    (net (code "139") (name "unconnected-(U$7-D3-PadJP2.5)") (class "Default")
      (node (ref "U$7") (pin "JP2.5") (pinfunction "D3_JP2.5") (pintype "bidirectional"))
    )
    (net (code "140") (name "unconnected-(U$7-D4-PadJP2.6)") (class "Default")
      (node (ref "U$7") (pin "JP2.6") (pinfunction "D4_JP2.6") (pintype "bidirectional"))
    )
    (net (code "141") (name "unconnected-(U$7-RST-PadJP1.1)") (class "Default")
      (node (ref "U$7") (pin "JP1.1") (pinfunction "RST_JP1.1") (pintype "bidirectional"))
    )
    (net (code "142") (name "unconnected-(U$7-RX-PadJP2.2)") (class "Default")
      (node (ref "U$7") (pin "JP2.2") (pinfunction "RX_JP2.2") (pintype "bidirectional"))
    )
    (net (code "143") (name "unconnected-(U$7-TX-PadJP2.1)") (class "Default")
      (node (ref "U$7") (pin "JP2.1") (pinfunction "TX_JP2.1") (pintype "bidirectional"))
    )
    (net (code "144") (name "unconnected-(U$10-PadDTR)") (class "Default")
      (node (ref "U$10") (pin "DTR") (pinfunction "DTR_DTR") (pintype "bidirectional"))
    )
    (net (code "145") (name "unconnected-(U$10-PadMIC+)") (class "Default")
      (node (ref "U$10") (pin "MIC+") (pinfunction "MIC+_MIC+") (pintype "bidirectional"))
    )
    (net (code "146") (name "unconnected-(U$10-PadMIC-)") (class "Default")
      (node (ref "U$10") (pin "MIC-") (pinfunction "MIC-_MIC-") (pintype "bidirectional"))
    )
    (net (code "147") (name "unconnected-(U$10-PadNET)") (class "Default")
      (node (ref "U$10") (pin "NET") (pinfunction "NET_NET") (pintype "bidirectional"))
    )
    (net (code "148") (name "unconnected-(U$10-PadRING)") (class "Default")
      (node (ref "U$10") (pin "RING") (pinfunction "RING_RING") (pintype "bidirectional"))
    )
    (net (code "149") (name "unconnected-(U$10-PadRST)") (class "Default")
      (node (ref "U$10") (pin "RST") (pinfunction "RST_RST") (pintype "bidirectional"))
    )
    (net (code "150") (name "unconnected-(U$10-PadSPK+)") (class "Default")
      (node (ref "U$10") (pin "SPK+") (pinfunction "SPK+_SPK+") (pintype "bidirectional"))
    )
    (net (code "151") (name "unconnected-(U$10-PadSPK-)") (class "Default")
      (node (ref "U$10") (pin "SPK-") (pinfunction "SPK-_SPK-") (pintype "bidirectional"))
    )
  )
)
